# coupon.net
KiCad netlist of a schematic drawn in EAGLE
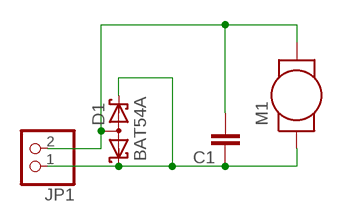
[diagram p0: schematic, sheet 1]

(export (version "E")
  (design (tool "Eeschema 10.0.6"))
  (components
    (comp (ref "C1")
      (value "C-EUC0805")
      (footprint "eagle-import:C0805")
      (libsource (lib "eagle-import") (part "C-EUC0805"))
    )
    (comp (ref "D1")
      (value "BAT54A")
      (footprint "eagle-import:SOT23")
      (libsource (lib "eagle-import") (part "BAT54A"))
    )
    (comp (ref "JP1")
      (value "PINHD-1X2")
      (footprint "eagle-import:1X02")
      (libsource (lib "eagle-import") (part "PINHD-1X2"))
    )
    (comp (ref "M1")
      (value "PAGER-PANCAKE")
      (footprint "eagle-import:PANCAKE")
      (libsource (lib "eagle-import") (part "PAGER-PANCAKE"))
    )
  )
  (nets
    (net (code "1") (name "Net-(D1-AA)") (class "Default")
      (node (ref "C1") (pin "2") (pinfunction "2_2") (pintype "passive"))
      (node (ref "D1") (pin "3") (pinfunction "AA_3") (pintype "passive"))
      (node (ref "JP1") (pin "2") (pinfunction "2_2") (pintype "passive"))
      (node (ref "M1") (pin "P$2") (pinfunction "P$2_P$2") (pintype "bidirectional"))
    )
    (net (code "2") (name "Net-(D1-K1)") (class "Default")
      (node (ref "C1") (pin "1") (pinfunction "1_1") (pintype "passive"))
      (node (ref "D1") (pin "1") (pinfunction "K1_1") (pintype "passive"))
      (node (ref "D1") (pin "2") (pinfunction "K2_2") (pintype "passive"))
      (node (ref "JP1") (pin "1") (pinfunction "1_1") (pintype "passive"))
      (node (ref "M1") (pin "P$1") (pinfunction "P$1_P$1") (pintype "bidirectional"))
    )
  )
)
